# action_module_base.net
KiCad netlist of a schematic drawn in EAGLE
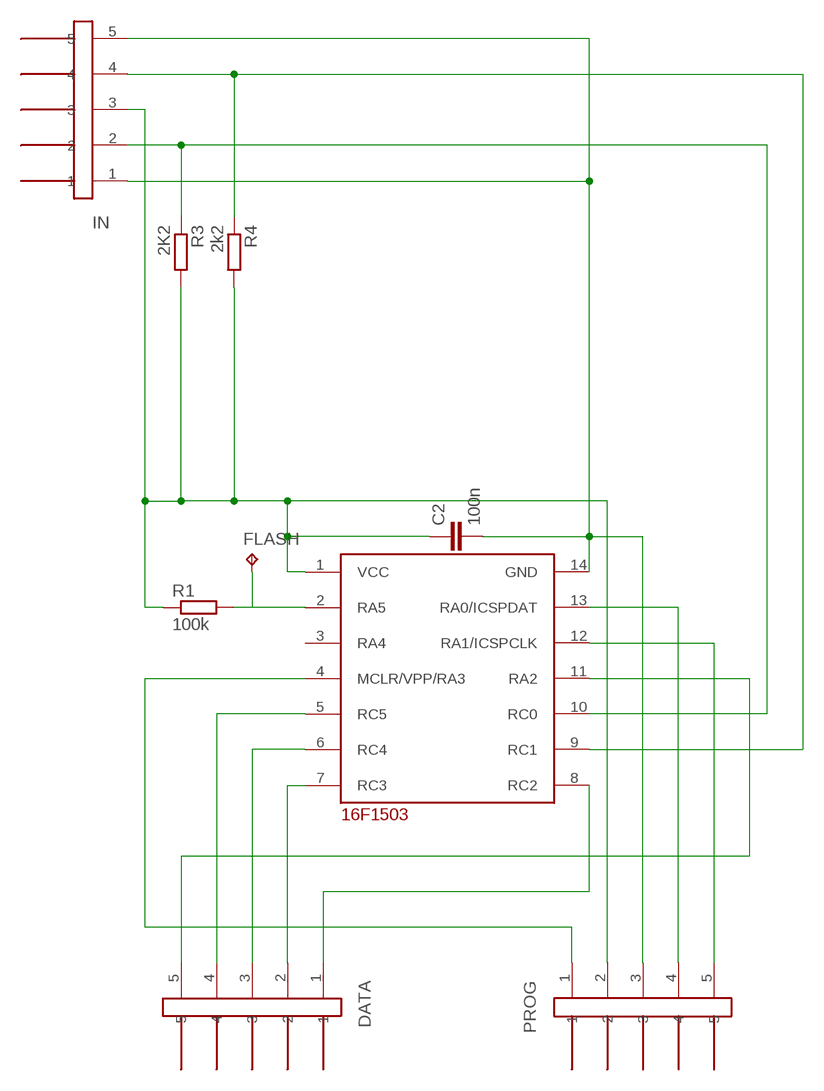
[diagram p0: schematic, sheet 1]

(export (version "E")
  (design (tool "Eeschema 10.0.6"))
  (components
    (comp (ref "C2")
      (value "100n")
      (footprint "eagle-import:C0603K")
      (libsource (lib "eagle-import") (part "C-EUC0603K"))
    )
    (comp (ref "DATA")
      (value "JUMPER5M")
      (footprint "eagle-import:JUMPER5M")
      (libsource (lib "eagle-import") (part "JUMPER5M"))
    )
    (comp (ref "FLASH")
      (value "TPTP10R")
      (footprint "eagle-import:TP10R")
      (libsource (lib "eagle-import") (part "TPTP10R"))
    )
    (comp (ref "IN")
      (value "JUMPER5M-90")
      (footprint "eagle-import:JUMPER5M-90")
      (libsource (lib "eagle-import") (part "JUMPER5M-90"))
    )
    (comp (ref "PROG")
      (value "JUMPER5M")
      (footprint "eagle-import:JUMPER5M")
      (libsource (lib "eagle-import") (part "JUMPER5M"))
    )
    (comp (ref "R1")
      (value "100k")
      (footprint "eagle-import:R0603")
      (libsource (lib "eagle-import") (part "R-EU_R0603"))
    )
    (comp (ref "R3")
      (value "2K2")
      (footprint "eagle-import:R0603")
      (libsource (lib "eagle-import") (part "R-EU_R0603"))
    )
    (comp (ref "R4")
      (value "2k2")
      (footprint "eagle-import:R0603")
      (libsource (lib "eagle-import") (part "R-EU_R0603"))
    )
    (comp (ref "U1")
      (value "16F103")
      (footprint "eagle-import:TSSOP14")
      (libsource (lib "eagle-import") (part "16F103-TSSOP"))
    )
  )
  (nets
    (net (code "1") (name "Net-(U1-GND)") (class "Default")
      (node (ref "C2") (pin "2") (pinfunction "2_2") (pintype "passive"))
      (node (ref "IN") (pin "1") (pinfunction "1_1") (pintype "bidirectional"))
      (node (ref "IN") (pin "5") (pinfunction "5_5") (pintype "bidirectional"))
      (node (ref "PROG") (pin "3") (pinfunction "3_3") (pintype "bidirectional"))
      (node (ref "U1") (pin "14") (pinfunction "GND_14") (pintype "power_in"))
    )
    (net (code "2") (name "Net-(U1-MCLR{slash}VPP{slash}RA3)") (class "Default")
      (node (ref "PROG") (pin "1") (pinfunction "1_1") (pintype "bidirectional"))
      (node (ref "U1") (pin "4") (pinfunction "MCLR/VPP/RA3_4") (pintype "bidirectional"))
    )
    (net (code "3") (name "Net-(U1-RA0{slash}ICSPDAT)") (class "Default")
      (node (ref "PROG") (pin "4") (pinfunction "4_4") (pintype "bidirectional"))
      (node (ref "U1") (pin "13") (pinfunction "RA0/ICSPDAT_13") (pintype "bidirectional"))
    )
    (net (code "4") (name "Net-(U1-RA1{slash}ICSPCLK)") (class "Default")
      (node (ref "PROG") (pin "5") (pinfunction "5_5") (pintype "bidirectional"))
      (node (ref "U1") (pin "12") (pinfunction "RA1/ICSPCLK_12") (pintype "bidirectional"))
    )
    (net (code "5") (name "Net-(U1-RA2)") (class "Default")
      (node (ref "DATA") (pin "5") (pinfunction "5_5") (pintype "bidirectional"))
      (node (ref "U1") (pin "11") (pinfunction "RA2_11") (pintype "bidirectional"))
    )
    (net (code "6") (name "Net-(U1-RA5)") (class "Default")
      (node (ref "FLASH") (pin "TP") (pinfunction "TP_TP") (pintype "input"))
      (node (ref "R1") (pin "2") (pinfunction "2_2") (pintype "passive"))
      (node (ref "U1") (pin "2") (pinfunction "RA5_2") (pintype "bidirectional"))
    )
    (net (code "7") (name "Net-(U1-RC0)") (class "Default")
      (node (ref "IN") (pin "2") (pinfunction "2_2") (pintype "bidirectional"))
      (node (ref "R3") (pin "1") (pinfunction "1_1") (pintype "passive"))
      (node (ref "U1") (pin "10") (pinfunction "RC0_10") (pintype "bidirectional"))
    )
    (net (code "8") (name "Net-(U1-RC1)") (class "Default")
      (node (ref "IN") (pin "4") (pinfunction "4_4") (pintype "bidirectional"))
      (node (ref "R4") (pin "1") (pinfunction "1_1") (pintype "passive"))
      (node (ref "U1") (pin "9") (pinfunction "RC1_9") (pintype "bidirectional"))
    )
    (net (code "9") (name "Net-(U1-RC2)") (class "Default")
      (node (ref "DATA") (pin "1") (pinfunction "1_1") (pintype "bidirectional"))
      (node (ref "U1") (pin "8") (pinfunction "RC2_8") (pintype "bidirectional"))
    )
    (net (code "10") (name "Net-(U1-RC3)") (class "Default")
      (node (ref "DATA") (pin "2") (pinfunction "2_2") (pintype "bidirectional"))
      (node (ref "U1") (pin "7") (pinfunction "RC3_7") (pintype "bidirectional"))
    )
    (net (code "11") (name "Net-(U1-RC4)") (class "Default")
      (node (ref "DATA") (pin "3") (pinfunction "3_3") (pintype "bidirectional"))
      (node (ref "U1") (pin "6") (pinfunction "RC4_6") (pintype "bidirectional"))
    )
    (net (code "12") (name "Net-(U1-RC5)") (class "Default")
      (node (ref "DATA") (pin "4") (pinfunction "4_4") (pintype "bidirectional"))
      (node (ref "U1") (pin "5") (pinfunction "RC5_5") (pintype "bidirectional"))
    )
    (net (code "13") (name "Net-(U1-VCC)") (class "Default")
      (node (ref "C2") (pin "1") (pinfunction "1_1") (pintype "passive"))
      (node (ref "IN") (pin "3") (pinfunction "3_3") (pintype "bidirectional"))
      (node (ref "PROG") (pin "2") (pinfunction "2_2") (pintype "bidirectional"))
      (node (ref "R1") (pin "1") (pinfunction "1_1") (pintype "passive"))
      (node (ref "R3") (pin "2") (pinfunction "2_2") (pintype "passive"))
      (node (ref "R4") (pin "2") (pinfunction "2_2") (pintype "passive"))
      (node (ref "U1") (pin "1") (pinfunction "VCC_1") (pintype "power_in"))
    )
    (net (code "14") (name "unconnected-(U1-RA4-Pad3)") (class "Default")
      (node (ref "U1") (pin "3") (pinfunction "RA4_3") (pintype "bidirectional"))
    )
  )
)
